# PCB_baseStation.net
KiCad netlist of a schematic drawn in EAGLE
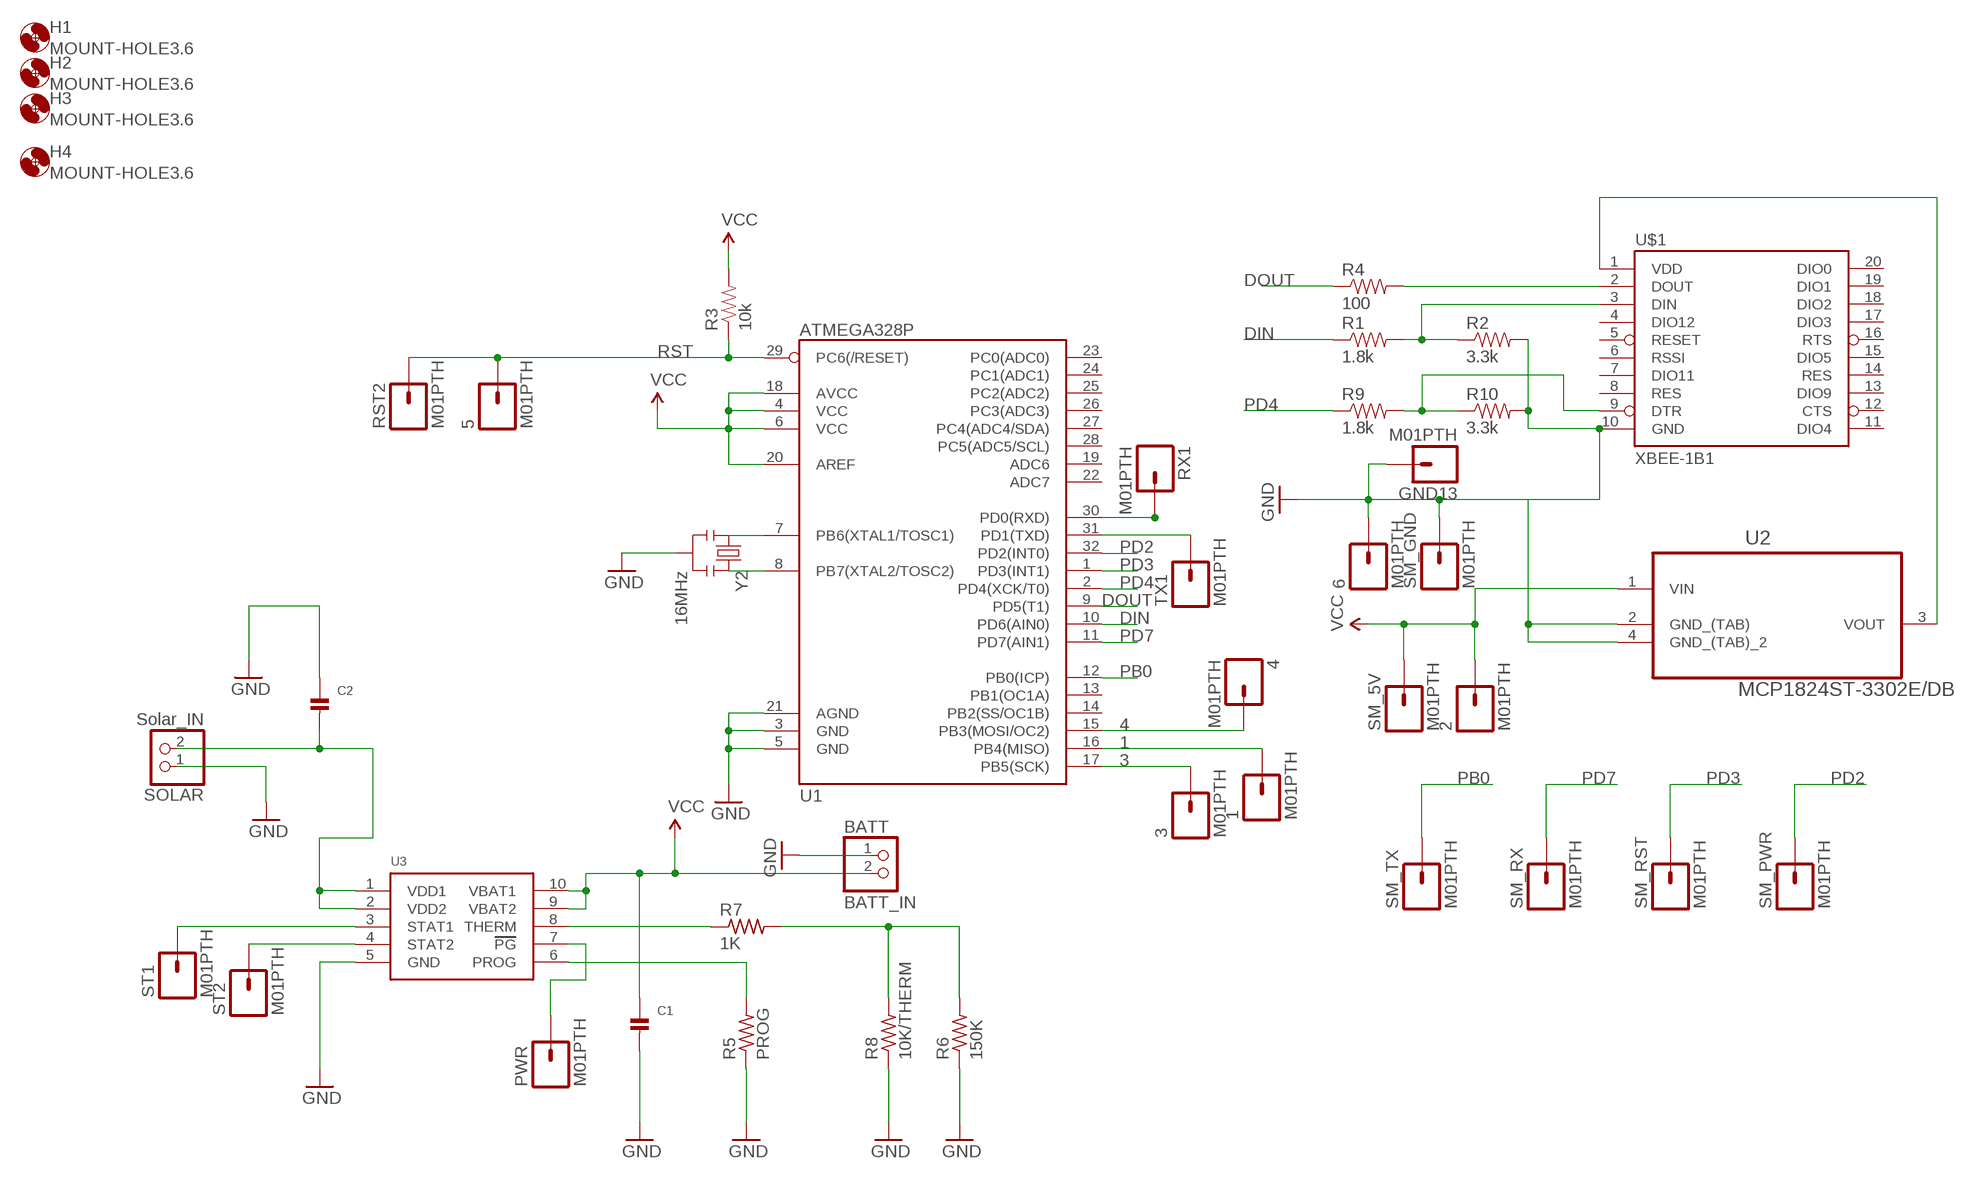
[diagram p0: schematic, sheet 1]

(export (version "E")
  (design (tool "Eeschema 10.0.6"))
  (components
    (comp (ref "1")
      (value "M01PTH")
      (footprint "eagle-import:1X01")
      (libsource (lib "eagle-import") (part "M01PTH"))
    )
    (comp (ref "2")
      (value "M01PTH")
      (footprint "eagle-import:1X01")
      (libsource (lib "eagle-import") (part "M01PTH"))
    )
    (comp (ref "3")
      (value "M01PTH")
      (footprint "eagle-import:1X01")
      (libsource (lib "eagle-import") (part "M01PTH"))
    )
    (comp (ref "4")
      (value "M01PTH")
      (footprint "eagle-import:1X01")
      (libsource (lib "eagle-import") (part "M01PTH"))
    )
    (comp (ref "5")
      (value "M01PTH")
      (footprint "eagle-import:1X01")
      (libsource (lib "eagle-import") (part "M01PTH"))
    )
    (comp (ref "6")
      (value "M01PTH")
      (footprint "eagle-import:1X01")
      (libsource (lib "eagle-import") (part "M01PTH"))
    )
    (comp (ref "BATT")
      (value "BATT_IN")
      (footprint "eagle-import:JSTPH2")
      (libsource (lib "eagle-import") (part "JST_2PIN"))
    )
    (comp (ref "C1")
      (value "CAP_CERAMIC0805")
      (footprint "eagle-import:0805")
      (libsource (lib "eagle-import") (part "CAP_CERAMIC0805"))
    )
    (comp (ref "C2")
      (value "CAP_CERAMIC0805")
      (footprint "eagle-import:0805")
      (libsource (lib "eagle-import") (part "CAP_CERAMIC0805"))
    )
    (comp (ref "GND13")
      (value "M01PTH")
      (footprint "eagle-import:1X01")
      (libsource (lib "eagle-import") (part "M01PTH"))
    )
    (comp (ref "H1")
      (value "MOUNT-HOLE3.6")
      (footprint "eagle-import:3,6")
      (libsource (lib "eagle-import") (part "MOUNT-HOLE3.6"))
    )
    (comp (ref "H2")
      (value "MOUNT-HOLE3.6")
      (footprint "eagle-import:3,6")
      (libsource (lib "eagle-import") (part "MOUNT-HOLE3.6"))
    )
    (comp (ref "H3")
      (value "MOUNT-HOLE3.6")
      (footprint "eagle-import:3,6")
      (libsource (lib "eagle-import") (part "MOUNT-HOLE3.6"))
    )
    (comp (ref "H4")
      (value "MOUNT-HOLE3.6")
      (footprint "eagle-import:3,6")
      (libsource (lib "eagle-import") (part "MOUNT-HOLE3.6"))
    )
    (comp (ref "PWR")
      (value "M01PTH")
      (footprint "eagle-import:1X01")
      (libsource (lib "eagle-import") (part "M01PTH"))
    )
    (comp (ref "R1")
      (value "1.8k")
      (footprint "eagle-import:0603-RES")
      (libsource (lib "eagle-import") (part "1.8KOHM1/10W1%(0603)"))
    )
    (comp (ref "R2")
      (value "3.3k")
      (footprint "eagle-import:0603-RES")
      (libsource (lib "eagle-import") (part "3.3KOHM1/10W1%(0603)"))
    )
    (comp (ref "R3")
      (value "10k")
      (footprint "eagle-import:1206")
      (libsource (lib "eagle-import") (part "RESISTOR1206"))
    )
    (comp (ref "R4")
      (value "100")
      (footprint "eagle-import:0603-RES")
      (libsource (lib "eagle-import") (part "100OHM1/10W1%(0603)"))
    )
    (comp (ref "R5")
      (value "PROG")
      (footprint "eagle-import:0805-THM")
      (libsource (lib "eagle-import") (part "RESISTOR_DUAL"))
    )
    (comp (ref "R6")
      (value "150K")
      (footprint "eagle-import:M0805")
      (libsource (lib "eagle-import") (part "R-US_M0805"))
    )
    (comp (ref "R7")
      (value "1K")
      (footprint "eagle-import:M0805")
      (libsource (lib "eagle-import") (part "R-US_M0805"))
    )
    (comp (ref "R8")
      (value "10K/THERM")
      (footprint "eagle-import:0805-THM")
      (libsource (lib "eagle-import") (part "R-US_FLIPFLOP"))
    )
    (comp (ref "R9")
      (value "1.8k")
      (footprint "eagle-import:0603-RES")
      (libsource (lib "eagle-import") (part "1.8KOHM1/10W1%(0603)"))
    )
    (comp (ref "R10")
      (value "3.3k")
      (footprint "eagle-import:0603-RES")
      (libsource (lib "eagle-import") (part "3.3KOHM1/10W1%(0603)"))
    )
    (comp (ref "RST2")
      (value "M01PTH")
      (footprint "eagle-import:1X01")
      (libsource (lib "eagle-import") (part "M01PTH"))
    )
    (comp (ref "RX1")
      (value "M01PTH")
      (footprint "eagle-import:1X01")
      (libsource (lib "eagle-import") (part "M01PTH"))
    )
    (comp (ref "SM_5V")
      (value "M01PTH")
      (footprint "eagle-import:1X01")
      (libsource (lib "eagle-import") (part "M01PTH"))
    )
    (comp (ref "SM_GND")
      (value "M01PTH")
      (footprint "eagle-import:1X01")
      (libsource (lib "eagle-import") (part "M01PTH"))
    )
    (comp (ref "SM_PWR")
      (value "M01PTH")
      (footprint "eagle-import:1X01")
      (libsource (lib "eagle-import") (part "M01PTH"))
    )
    (comp (ref "SM_RST")
      (value "M01PTH")
      (footprint "eagle-import:1X01")
      (libsource (lib "eagle-import") (part "M01PTH"))
    )
    (comp (ref "SM_RX")
      (value "M01PTH")
      (footprint "eagle-import:1X01")
      (libsource (lib "eagle-import") (part "M01PTH"))
    )
    (comp (ref "SM_TX")
      (value "M01PTH")
      (footprint "eagle-import:1X01")
      (libsource (lib "eagle-import") (part "M01PTH"))
    )
    (comp (ref "SOLAR")
      (value "Solar_IN")
      (footprint "eagle-import:JSTPH2")
      (libsource (lib "eagle-import") (part "JST_2PIN"))
    )
    (comp (ref "ST1")
      (value "M01PTH")
      (footprint "eagle-import:1X01")
      (libsource (lib "eagle-import") (part "M01PTH"))
    )
    (comp (ref "ST2")
      (value "M01PTH")
      (footprint "eagle-import:1X01")
      (libsource (lib "eagle-import") (part "M01PTH"))
    )
    (comp (ref "TX1")
      (value "M01PTH")
      (footprint "eagle-import:1X01")
      (libsource (lib "eagle-import") (part "M01PTH"))
    )
    (comp (ref "U$1")
      (value "XBEE-1B1")
      (footprint "eagle-import:XBEE-1")
      (libsource (lib "eagle-import") (part "XBEE-1B1"))
    )
    (comp (ref "U1")
      (value "ATMEGA328P")
      (footprint "eagle-import:TQFP32-08")
      (libsource (lib "eagle-import") (part "ATMEGA328_SMT"))
    )
    (comp (ref "U2")
      (value "MCP1824ST-3302E/DB")
      (footprint "eagle-import:SOT230P700X180-4N")
      (libsource (lib "eagle-import") (part "MCP1824ST-3302E/DB"))
    )
    (comp (ref "U3")
      (value "MCP73833")
      (footprint "eagle-import:MSOP10")
      (libsource (lib "eagle-import") (part "MCP73833"))
    )
    (comp (ref "Y2")
      (value "16MHz")
      (footprint "eagle-import:RESONATOR-SMD")
      (libsource (lib "eagle-import") (part "RESONATOR16MHZ"))
    )
  )
  (nets
    (net (code "1") (name "/1") (class "Default")
      (node (ref "1") (pin "1") (pinfunction "1_1") (pintype "passive"))
      (node (ref "U1") (pin "16") (pinfunction "PB4(MISO)_16") (pintype "bidirectional"))
    )
    (net (code "2") (name "/3") (class "Default")
      (node (ref "3") (pin "1") (pinfunction "1_1") (pintype "passive"))
      (node (ref "U1") (pin "17") (pinfunction "PB5(SCK)_17") (pintype "bidirectional"))
    )
    (net (code "3") (name "/4") (class "Default")
      (node (ref "4") (pin "1") (pinfunction "1_1") (pintype "passive"))
      (node (ref "U1") (pin "15") (pinfunction "PB3(MOSI/OC2)_15") (pintype "bidirectional"))
    )
    (net (code "4") (name "/DIN") (class "Default")
      (node (ref "R1") (pin "1") (pinfunction "1_1") (pintype "passive"))
      (node (ref "U1") (pin "10") (pinfunction "PD6(AIN0)_10") (pintype "bidirectional"))
    )
    (net (code "5") (name "/DOUT") (class "Default")
      (node (ref "R4") (pin "1") (pinfunction "1_1") (pintype "passive"))
      (node (ref "U1") (pin "9") (pinfunction "PD5(T1)_9") (pintype "bidirectional"))
    )
    (net (code "6") (name "/PB0") (class "Default")
      (node (ref "SM_TX") (pin "1") (pinfunction "1_1") (pintype "passive"))
      (node (ref "U1") (pin "12") (pinfunction "PB0(ICP)_12") (pintype "bidirectional"))
    )
    (net (code "7") (name "/PD2") (class "Default")
      (node (ref "SM_PWR") (pin "1") (pinfunction "1_1") (pintype "passive"))
      (node (ref "U1") (pin "32") (pinfunction "PD2(INT0)_32") (pintype "bidirectional"))
    )
    (net (code "8") (name "/PD3") (class "Default")
      (node (ref "SM_RST") (pin "1") (pinfunction "1_1") (pintype "passive"))
      (node (ref "U1") (pin "1") (pinfunction "PD3(INT1)_1") (pintype "bidirectional"))
    )
    (net (code "9") (name "/PD4") (class "Default")
      (node (ref "R9") (pin "1") (pinfunction "1_1") (pintype "passive"))
      (node (ref "U1") (pin "2") (pinfunction "PD4(XCK/T0)_2") (pintype "bidirectional"))
    )
    (net (code "10") (name "/PD7") (class "Default")
      (node (ref "SM_RX") (pin "1") (pinfunction "1_1") (pintype "passive"))
      (node (ref "U1") (pin "11") (pinfunction "PD7(AIN1)_11") (pintype "bidirectional"))
    )
    (net (code "11") (name "/RST") (class "Default")
      (node (ref "5") (pin "1") (pinfunction "1_1") (pintype "passive"))
      (node (ref "R3") (pin "1") (pinfunction "1_1") (pintype "passive"))
      (node (ref "RST2") (pin "1") (pinfunction "1_1") (pintype "passive"))
      (node (ref "U1") (pin "29") (pinfunction "PC6(/RESET)_29") (pintype "bidirectional"))
    )
    (net (code "12") (name "GND") (class "Default")
      (node (ref "6") (pin "1") (pinfunction "1_1") (pintype "passive"))
      (node (ref "BATT") (pin "1") (pinfunction "1_1") (pintype "passive"))
      (node (ref "C1") (pin "2") (pinfunction "P$2_2") (pintype "passive"))
      (node (ref "C2") (pin "1") (pinfunction "P$1_1") (pintype "passive"))
      (node (ref "GND13") (pin "1") (pinfunction "1_1") (pintype "passive"))
      (node (ref "R10") (pin "2") (pinfunction "2_2") (pintype "passive"))
      (node (ref "R2") (pin "2") (pinfunction "2_2") (pintype "passive"))
      (node (ref "R5") (pin "1") (pinfunction "1_1") (pintype "passive"))
      (node (ref "R6") (pin "1") (pinfunction "1_1") (pintype "passive"))
      (node (ref "R8") (pin "1") (pinfunction "1_1") (pintype "passive"))
      (node (ref "SM_GND") (pin "1") (pinfunction "1_1") (pintype "passive"))
      (node (ref "SOLAR") (pin "1") (pinfunction "1_1") (pintype "passive"))
      (node (ref "U$1") (pin "10") (pinfunction "GND_10") (pintype "power_in"))
      (node (ref "U1") (pin "21") (pinfunction "AGND_21") (pintype "bidirectional"))
      (node (ref "U1") (pin "3") (pinfunction "GND_3") (pintype "bidirectional"))
      (node (ref "U1") (pin "5") (pinfunction "GND_5") (pintype "bidirectional"))
      (node (ref "U2") (pin "2") (pinfunction "GND_(TAB)_2") (pintype "passive"))
      (node (ref "U2") (pin "4") (pinfunction "GND_(TAB)_2_4") (pintype "passive"))
      (node (ref "U3") (pin "5") (pinfunction "GND_5") (pintype "bidirectional"))
      (node (ref "Y2") (pin "2") (pinfunction "2_2") (pintype "passive"))
    )
    (net (code "13") (name "Net-(C2-P$2)") (class "Default")
      (node (ref "C2") (pin "2") (pinfunction "P$2_2") (pintype "passive"))
      (node (ref "SOLAR") (pin "2") (pinfunction "2_2") (pintype "passive"))
      (node (ref "U3") (pin "1") (pinfunction "VDD1_1") (pintype "bidirectional"))
      (node (ref "U3") (pin "2") (pinfunction "VDD2_2") (pintype "bidirectional"))
    )
    (net (code "14") (name "Net-(R6-Pad2)") (class "Default")
      (node (ref "R6") (pin "2") (pinfunction "2_2") (pintype "passive"))
      (node (ref "R7") (pin "2") (pinfunction "2_2") (pintype "passive"))
      (node (ref "R8") (pin "2") (pinfunction "2_2") (pintype "passive"))
    )
    (net (code "15") (name "Net-(U$1-DIN)") (class "Default")
      (node (ref "R1") (pin "2") (pinfunction "2_2") (pintype "passive"))
      (node (ref "R2") (pin "1") (pinfunction "1_1") (pintype "passive"))
      (node (ref "U$1") (pin "3") (pinfunction "DIN_3") (pintype "input"))
    )
    (net (code "16") (name "Net-(U$1-DOUT)") (class "Default")
      (node (ref "R4") (pin "2") (pinfunction "2_2") (pintype "passive"))
      (node (ref "U$1") (pin "2") (pinfunction "DOUT_2") (pintype "output"))
    )
    (net (code "17") (name "Net-(U$1-DTR)") (class "Default")
      (node (ref "R10") (pin "1") (pinfunction "1_1") (pintype "passive"))
      (node (ref "R9") (pin "2") (pinfunction "2_2") (pintype "passive"))
      (node (ref "U$1") (pin "9") (pinfunction "DTR_9") (pintype "bidirectional"))
    )
    (net (code "18") (name "Net-(U$1-VDD)") (class "Default")
      (node (ref "U$1") (pin "1") (pinfunction "VDD_1") (pintype "power_in"))
      (node (ref "U2") (pin "3") (pinfunction "VOUT_3") (pintype "output"))
    )
    (net (code "19") (name "Net-(U1-PB6(XTAL1{slash}TOSC1))") (class "Default")
      (node (ref "U1") (pin "7") (pinfunction "PB6(XTAL1/TOSC1)_7") (pintype "bidirectional"))
      (node (ref "Y2") (pin "1") (pinfunction "1_1") (pintype "passive"))
    )
    (net (code "20") (name "Net-(U1-PB7(XTAL2{slash}TOSC2))") (class "Default")
      (node (ref "U1") (pin "8") (pinfunction "PB7(XTAL2/TOSC2)_8") (pintype "bidirectional"))
      (node (ref "Y2") (pin "3") (pinfunction "3_3") (pintype "passive"))
    )
    (net (code "21") (name "Net-(U1-PD0(RXD))") (class "Default")
      (node (ref "RX1") (pin "1") (pinfunction "1_1") (pintype "passive"))
      (node (ref "U1") (pin "30") (pinfunction "PD0(RXD)_30") (pintype "bidirectional"))
    )
    (net (code "22") (name "Net-(U1-PD1(TXD))") (class "Default")
      (node (ref "TX1") (pin "1") (pinfunction "1_1") (pintype "passive"))
      (node (ref "U1") (pin "31") (pinfunction "PD1(TXD)_31") (pintype "bidirectional"))
    )
    (net (code "23") (name "Net-(U3-PG)") (class "Default")
      (node (ref "PWR") (pin "1") (pinfunction "1_1") (pintype "passive"))
      (node (ref "U3") (pin "7") (pinfunction "PG_7") (pintype "bidirectional"))
    )
    (net (code "24") (name "Net-(U3-PROG)") (class "Default")
      (node (ref "R5") (pin "2") (pinfunction "2_2") (pintype "passive"))
      (node (ref "U3") (pin "6") (pinfunction "PROG_6") (pintype "bidirectional"))
    )
    (net (code "25") (name "Net-(U3-STAT1)") (class "Default")
      (node (ref "ST1") (pin "1") (pinfunction "1_1") (pintype "passive"))
      (node (ref "U3") (pin "3") (pinfunction "STAT1_3") (pintype "bidirectional"))
    )
    (net (code "26") (name "Net-(U3-STAT2)") (class "Default")
      (node (ref "ST2") (pin "1") (pinfunction "1_1") (pintype "passive"))
      (node (ref "U3") (pin "4") (pinfunction "STAT2_4") (pintype "bidirectional"))
    )
    (net (code "27") (name "Net-(U3-THERM)") (class "Default")
      (node (ref "R7") (pin "1") (pinfunction "1_1") (pintype "passive"))
      (node (ref "U3") (pin "8") (pinfunction "THERM_8") (pintype "bidirectional"))
    )
    (net (code "28") (name "VCC") (class "Default")
      (node (ref "2") (pin "1") (pinfunction "1_1") (pintype "passive"))
      (node (ref "BATT") (pin "2") (pinfunction "2_2") (pintype "passive"))
      (node (ref "C1") (pin "1") (pinfunction "P$1_1") (pintype "passive"))
      (node (ref "R3") (pin "2") (pinfunction "2_2") (pintype "passive"))
      (node (ref "SM_5V") (pin "1") (pinfunction "1_1") (pintype "passive"))
      (node (ref "U1") (pin "18") (pinfunction "AVCC_18") (pintype "bidirectional"))
      (node (ref "U1") (pin "20") (pinfunction "AREF_20") (pintype "bidirectional"))
      (node (ref "U1") (pin "4") (pinfunction "VCC_4") (pintype "bidirectional"))
      (node (ref "U1") (pin "6") (pinfunction "VCC_6") (pintype "bidirectional"))
      (node (ref "U2") (pin "1") (pinfunction "VIN_1") (pintype "input"))
      (node (ref "U3") (pin "10") (pinfunction "VBAT1_10") (pintype "bidirectional"))
      (node (ref "U3") (pin "9") (pinfunction "VBAT2_9") (pintype "bidirectional"))
    )
    (net (code "29") (name "unconnected-(U$1-CTS-Pad12)") (class "Default")
      (node (ref "U$1") (pin "12") (pinfunction "CTS_12") (pintype "output"))
    )
    (net (code "30") (name "unconnected-(U$1-DIO0-Pad20)") (class "Default")
      (node (ref "U$1") (pin "20") (pinfunction "DIO0_20") (pintype "bidirectional"))
    )
    (net (code "31") (name "unconnected-(U$1-DIO1-Pad19)") (class "Default")
      (node (ref "U$1") (pin "19") (pinfunction "DIO1_19") (pintype "bidirectional"))
    )
    (net (code "32") (name "unconnected-(U$1-DIO2-Pad18)") (class "Default")
      (node (ref "U$1") (pin "18") (pinfunction "DIO2_18") (pintype "bidirectional"))
    )
    (net (code "33") (name "unconnected-(U$1-DIO3-Pad17)") (class "Default")
      (node (ref "U$1") (pin "17") (pinfunction "DIO3_17") (pintype "bidirectional"))
    )
    (net (code "34") (name "unconnected-(U$1-DIO4-Pad11)") (class "Default")
      (node (ref "U$1") (pin "11") (pinfunction "DIO4_11") (pintype "bidirectional"))
    )
    (net (code "35") (name "unconnected-(U$1-DIO5-Pad15)") (class "Default")
      (node (ref "U$1") (pin "15") (pinfunction "DIO5_15") (pintype "bidirectional"))
    )
    (net (code "36") (name "unconnected-(U$1-DIO9-Pad13)") (class "Default")
      (node (ref "U$1") (pin "13") (pinfunction "DIO9_13") (pintype "bidirectional"))
    )
    (net (code "37") (name "unconnected-(U$1-DIO11-Pad7)") (class "Default")
      (node (ref "U$1") (pin "7") (pinfunction "DIO11_7") (pintype "bidirectional"))
    )
    (net (code "38") (name "unconnected-(U$1-DIO12-Pad4)") (class "Default")
      (node (ref "U$1") (pin "4") (pinfunction "DIO12_4") (pintype "bidirectional"))
    )
    (net (code "39") (name "unconnected-(U$1-RES-Pad8)") (class "Default")
      (node (ref "U$1") (pin "8") (pinfunction "RES_8") (pintype "bidirectional"))
    )
    (net (code "40") (name "unconnected-(U$1-RES-Pad14)") (class "Default")
      (node (ref "U$1") (pin "14") (pinfunction "RES_14") (pintype "bidirectional"))
    )
    (net (code "41") (name "unconnected-(U$1-RESET-Pad5)") (class "Default")
      (node (ref "U$1") (pin "5") (pinfunction "RESET_5") (pintype "input"))
    )
    (net (code "42") (name "unconnected-(U$1-RSSI-Pad6)") (class "Default")
      (node (ref "U$1") (pin "6") (pinfunction "RSSI_6") (pintype "bidirectional"))
    )
    (net (code "43") (name "unconnected-(U$1-RTS-Pad16)") (class "Default")
      (node (ref "U$1") (pin "16") (pinfunction "RTS_16") (pintype "input"))
    )
    (net (code "44") (name "unconnected-(U1-ADC6-Pad19)") (class "Default")
      (node (ref "U1") (pin "19") (pinfunction "ADC6_19") (pintype "bidirectional"))
    )
    (net (code "45") (name "unconnected-(U1-ADC7-Pad22)") (class "Default")
      (node (ref "U1") (pin "22") (pinfunction "ADC7_22") (pintype "bidirectional"))
    )
    (net (code "46") (name "unconnected-(U1-PB1(OC1A)-Pad13)") (class "Default")
      (node (ref "U1") (pin "13") (pinfunction "PB1(OC1A)_13") (pintype "bidirectional"))
    )
    (net (code "47") (name "unconnected-(U1-PB2(SS{slash}OC1B)-Pad14)") (class "Default")
      (node (ref "U1") (pin "14") (pinfunction "PB2(SS/OC1B)_14") (pintype "bidirectional"))
    )
    (net (code "48") (name "unconnected-(U1-PC0(ADC0)-Pad23)") (class "Default")
      (node (ref "U1") (pin "23") (pinfunction "PC0(ADC0)_23") (pintype "bidirectional"))
    )
    (net (code "49") (name "unconnected-(U1-PC1(ADC1)-Pad24)") (class "Default")
      (node (ref "U1") (pin "24") (pinfunction "PC1(ADC1)_24") (pintype "bidirectional"))
    )
    (net (code "50") (name "unconnected-(U1-PC2(ADC2)-Pad25)") (class "Default")
      (node (ref "U1") (pin "25") (pinfunction "PC2(ADC2)_25") (pintype "bidirectional"))
    )
    (net (code "51") (name "unconnected-(U1-PC3(ADC3)-Pad26)") (class "Default")
      (node (ref "U1") (pin "26") (pinfunction "PC3(ADC3)_26") (pintype "bidirectional"))
    )
    (net (code "52") (name "unconnected-(U1-PC4(ADC4{slash}SDA)-Pad27)") (class "Default")
      (node (ref "U1") (pin "27") (pinfunction "PC4(ADC4/SDA)_27") (pintype "bidirectional"))
    )
    (net (code "53") (name "unconnected-(U1-PC5(ADC5{slash}SCL)-Pad28)") (class "Default")
      (node (ref "U1") (pin "28") (pinfunction "PC5(ADC5/SCL)_28") (pintype "bidirectional"))
    )
  )
)
